# Sheet1.net
KiCad netlist of a schematic drawn in Altium Designer
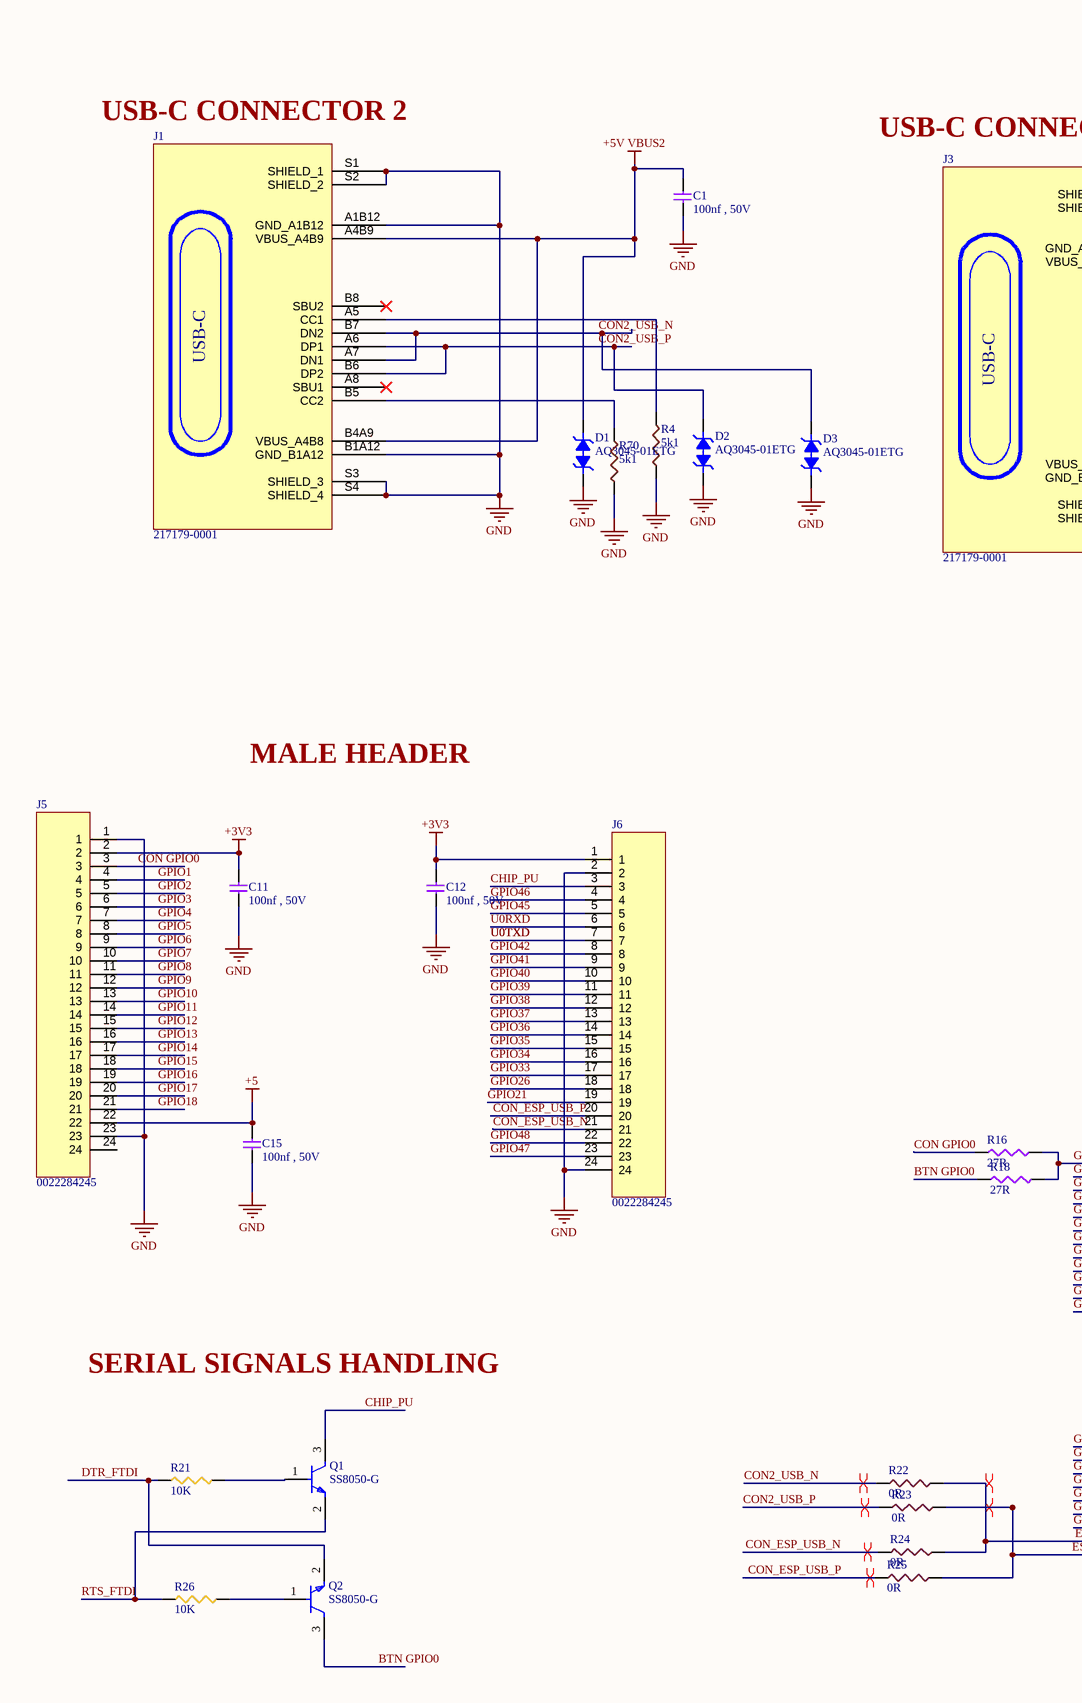
[diagram p0: Sheet1.SchDoc, left]
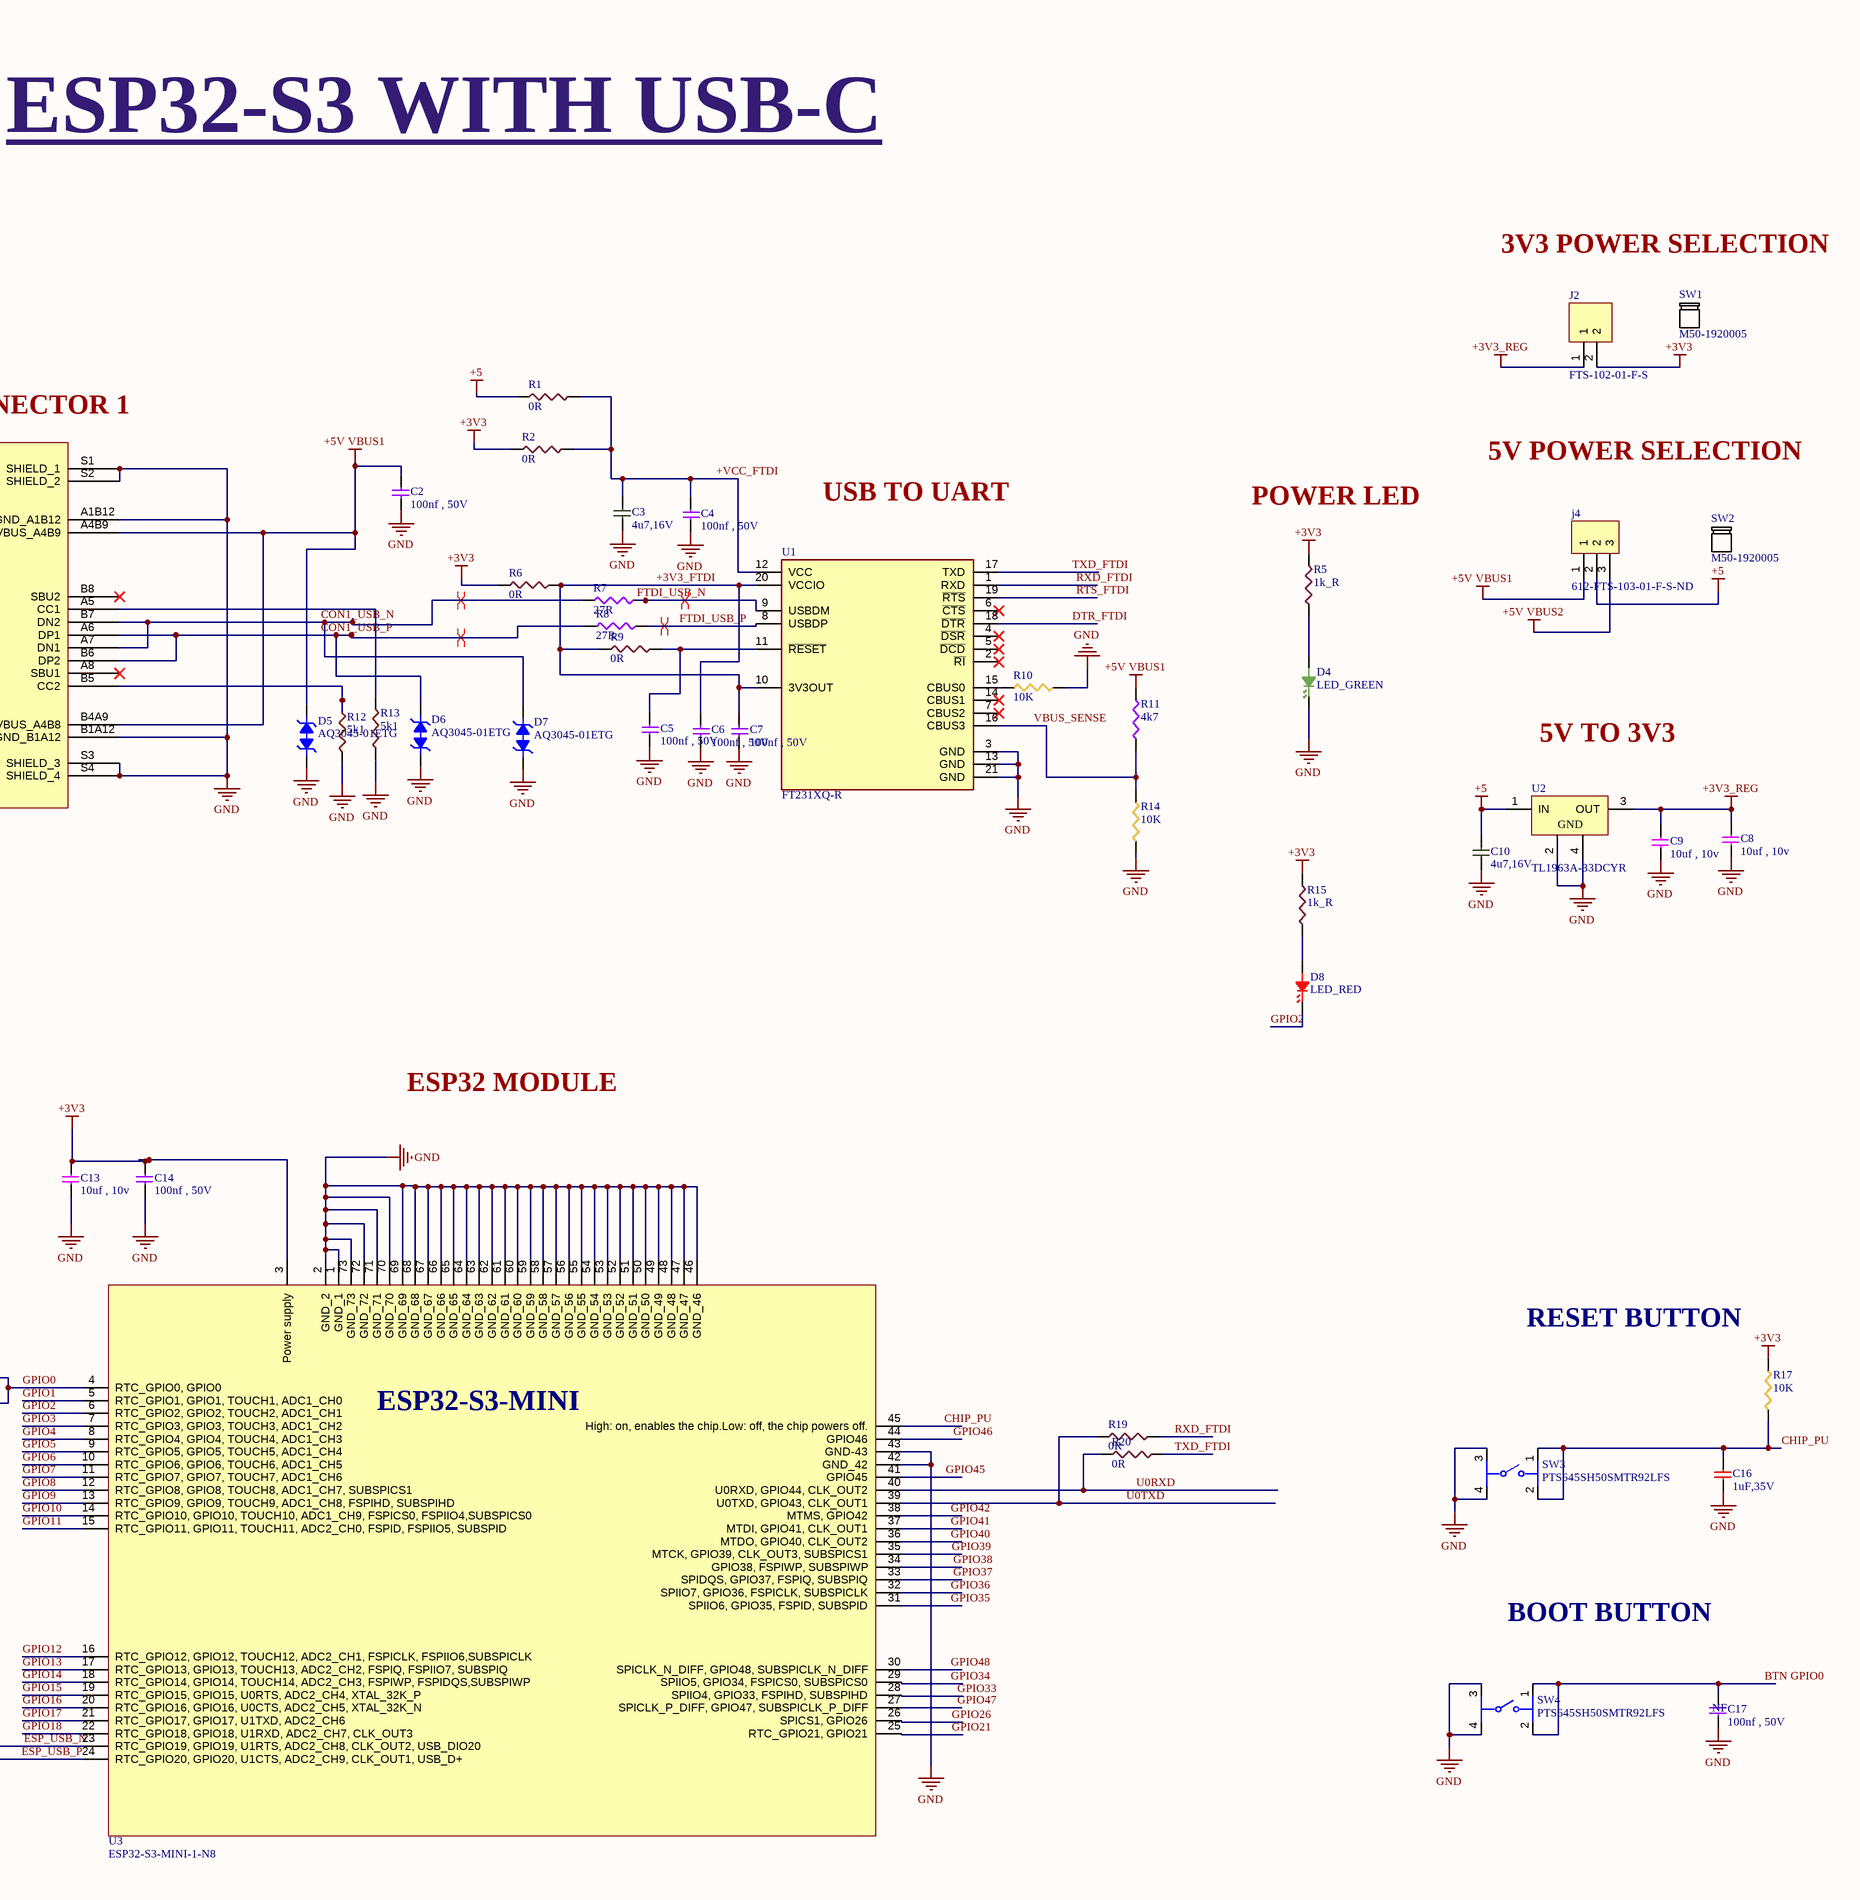
[diagram p1: Sheet1.SchDoc, right]

(export (version "E")
  (design (tool "Eeschema 10.0.6"))
  (components
    (comp (ref "C1")
      (value "100nf , 50V")
      (footprint "CAPC1005X55N")
      (fields
        (field (name "MANUFACTURER") "Samsung")
        (field (name "MANUFACTURER PART NUMBER") "CL05B104KB5NNNC")
        (field (name "TOLERANCE") "10%")
      )
      (libsource (lib "Schlib4") (part "CL05B104KB5NNNC"))
    )
    (comp (ref "C2")
      (value "100nf , 50V")
      (footprint "CAPC1005X55N")
      (fields
        (field (name "MANUFACTURER") "Samsung")
        (field (name "MANUFACTURER PART NUMBER") "CL05B104KB5NNNC")
        (field (name "TOLERANCE") "10%")
      )
      (libsource (lib "Schlib4") (part "CL05B104KB5NNNC"))
    )
    (comp (ref "C3")
      (value "4u7,16V")
      (footprint "CAPC1005X55N")
      (description "Multilayer Ceramic Capacitor, 4.7 uF, 16 V, ± 20%, X5R, 0402 [1005 Metric]")
      (fields
        (field (name "MANUFACTURER") "Samsung")
        (field (name "MANUFACTURER PART NUMBER") "CL05A475MO5NUNC")
      )
      (libsource (lib "Schlib4") (part "CL05A475MO5NUNC"))
    )
    (comp (ref "C4")
      (value "100nf , 50V")
      (footprint "CAPC1005X55N")
      (fields
        (field (name "MANUFACTURER") "Samsung")
        (field (name "MANUFACTURER PART NUMBER") "CL05B104KB5NNNC")
        (field (name "TOLERANCE") "10%")
      )
      (libsource (lib "Schlib4") (part "CL05B104KB5NNNC"))
    )
    (comp (ref "C5")
      (value "100nf , 50V")
      (footprint "CAPC1005X55N")
      (fields
        (field (name "MANUFACTURER") "Samsung")
        (field (name "MANUFACTURER PART NUMBER") "CL05B104KB5NNNC")
        (field (name "TOLERANCE") "10%")
      )
      (libsource (lib "Schlib4") (part "CL05B104KB5NNNC"))
    )
    (comp (ref "C6")
      (value "100nf , 50V")
      (footprint "CAPC1005X55N")
      (fields
        (field (name "MANUFACTURER") "Samsung")
        (field (name "MANUFACTURER PART NUMBER") "CL05B104KB5NNNC")
        (field (name "TOLERANCE") "10%")
      )
      (libsource (lib "Schlib4") (part "CL05B104KB5NNNC"))
    )
    (comp (ref "C7")
      (value "100nf , 50V")
      (footprint "CAPC1005X55N")
      (fields
        (field (name "MANUFACTURER") "Samsung")
        (field (name "MANUFACTURER PART NUMBER") "CL05B104KB5NNNC")
        (field (name "TOLERANCE") "10%")
      )
      (libsource (lib "Schlib4") (part "CL05B104KB5NNNC"))
    )
    (comp (ref "C8")
      (value "10uf , 10v")
      (footprint "CAPC1005X55N")
      (description "Multilayer Ceramic Capacitor, 10 uF, 10 V, ± 20%, X5R, 0402 [1005 Metric]")
      (fields
        (field (name "MANUFACTURER") "Samsung")
        (field (name "MANUFACTURER PART NUMBER") "CL05A106MP8NUB8")
      )
      (libsource (lib "Schlib4") (part "CL05A106MP8NUB8"))
    )
    (comp (ref "C9")
      (value "10uf , 10v")
      (footprint "CAPC1005X55N")
      (description "Multilayer Ceramic Capacitor, 10 uF, 10 V, ± 20%, X5R, 0402 [1005 Metric]")
      (fields
        (field (name "MANUFACTURER") "Samsung")
        (field (name "MANUFACTURER PART NUMBER") "CL05A106MP8NUB8")
      )
      (libsource (lib "Schlib4") (part "CL05A106MP8NUB8"))
    )
    (comp (ref "C10")
      (value "4u7,16V")
      (footprint "CAPC1005X55N")
      (description "Multilayer Ceramic Capacitor, 4.7 uF, 16 V, ± 20%, X5R, 0402 [1005 Metric]")
      (fields
        (field (name "MANUFACTURER") "Samsung")
        (field (name "MANUFACTURER PART NUMBER") "CL05A475MO5NUNC")
      )
      (libsource (lib "Schlib4") (part "CL05A475MO5NUNC"))
    )
    (comp (ref "C11")
      (value "100nf , 50V")
      (footprint "CAPC1005X55N")
      (fields
        (field (name "MANUFACTURER") "Samsung")
        (field (name "MANUFACTURER PART NUMBER") "CL05B104KB5NNNC")
        (field (name "TOLERANCE") "10%")
      )
      (libsource (lib "Schlib4") (part "CL05B104KB5NNNC"))
    )
    (comp (ref "C12")
      (value "100nf , 50V")
      (footprint "CAPC1005X55N")
      (fields
        (field (name "MANUFACTURER") "Samsung")
        (field (name "MANUFACTURER PART NUMBER") "CL05B104KB5NNNC")
        (field (name "TOLERANCE") "10%")
      )
      (libsource (lib "Schlib4") (part "CL05B104KB5NNNC"))
    )
    (comp (ref "C13")
      (value "10uf , 10v")
      (footprint "CAPC1005X55N")
      (description "Multilayer Ceramic Capacitor, 10 uF, 10 V, ± 20%, X5R, 0402 [1005 Metric]")
      (fields
        (field (name "MANUFACTURER") "Samsung")
        (field (name "MANUFACTURER PART NUMBER") "CL05A106MP8NUB8")
      )
      (libsource (lib "Schlib4") (part "CL05A106MP8NUB8"))
    )
    (comp (ref "C14")
      (value "100nf , 50V")
      (footprint "CAPC1005X55N")
      (fields
        (field (name "MANUFACTURER") "Samsung")
        (field (name "MANUFACTURER PART NUMBER") "CL05B104KB5NNNC")
        (field (name "TOLERANCE") "10%")
      )
      (libsource (lib "Schlib4") (part "CL05B104KB5NNNC"))
    )
    (comp (ref "C15")
      (value "100nf , 50V")
      (footprint "CAPC1005X55N")
      (fields
        (field (name "MANUFACTURER") "Samsung")
        (field (name "MANUFACTURER PART NUMBER") "CL05B104KB5NNNC")
        (field (name "TOLERANCE") "10%")
      )
      (libsource (lib "Schlib4") (part "CL05B104KB5NNNC"))
    )
    (comp (ref "C16")
      (value "1uF,35V")
      (footprint "CAPC1005X55N")
      (fields
        (field (name "MANUFACTURER") "Samsung")
        (field (name "MANUFACTURER PART NUMBER") "CL05A105KL5NRNC")
        (field (name "TOLERANCE") "10%")
      )
      (libsource (lib "Schlib4") (part "CL05A105KL5NRNC"))
    )
    (comp (ref "C17")
      (value "100nf , 50V")
      (footprint "CAPC1005X55N")
      (fields
        (field (name "MANUFACTURER") "Samsung")
        (field (name "MANUFACTURER PART NUMBER") "CL05B104KB5NNNC")
        (field (name "TOLERANCE") "10%")
      )
      (libsource (lib "Schlib4") (part "CL05B104KB5NNNC"))
    )
    (comp (ref "D1")
      (value "AQ3045-01ETG")
      (footprint "AQ3045-01ETG")
      (description "TVS DIODE 12VC 3A SOD882 / ESD Suppressor TVS Bi-Dir 5.3V Automotive 2-Pin SOD-882 T/R")
      (fields (field (name "MANUFACTURER") "Littelfuse"))
      (libsource (lib "Schlib4") (part "AQ3045-01ETG"))
    )
    (comp (ref "D2")
      (value "AQ3045-01ETG")
      (footprint "AQ3045-01ETG")
      (description "TVS DIODE 12VC 3A SOD882 / ESD Suppressor TVS Bi-Dir 5.3V Automotive 2-Pin SOD-882 T/R")
      (fields (field (name "MANUFACTURER") "Littelfuse"))
      (libsource (lib "Schlib4") (part "AQ3045-01ETG"))
    )
    (comp (ref "D3")
      (value "AQ3045-01ETG")
      (footprint "AQ3045-01ETG")
      (description "TVS DIODE 12VC 3A SOD882 / ESD Suppressor TVS Bi-Dir 5.3V Automotive 2-Pin SOD-882 T/R")
      (fields (field (name "MANUFACTURER") "Littelfuse"))
      (libsource (lib "Schlib4") (part "AQ3045-01ETG"))
    )
    (comp (ref "D4")
      (value "LED_GREEN")
      (footprint "LED_0402_GRN - duplicate")
      (description "LED Uni-Color Yellow Green 574nm 2-Pin Chip 0402(1006Metric) T/R")
      (fields
        (field (name "MANUFACTURER") "Vishay")
        (field (name "MANUFACTURER PART NUMBER") "VLMG1500-GS08")
      )
      (libsource (lib "Schlib4") (part "VLMG1500-GS08"))
    )
    (comp (ref "D5")
      (value "AQ3045-01ETG")
      (footprint "AQ3045-01ETG")
      (description "TVS DIODE 12VC 3A SOD882 / ESD Suppressor TVS Bi-Dir 5.3V Automotive 2-Pin SOD-882 T/R")
      (fields (field (name "MANUFACTURER") "Littelfuse"))
      (libsource (lib "Schlib4") (part "AQ3045-01ETG"))
    )
    (comp (ref "D6")
      (value "AQ3045-01ETG")
      (footprint "AQ3045-01ETG")
      (description "TVS DIODE 12VC 3A SOD882 / ESD Suppressor TVS Bi-Dir 5.3V Automotive 2-Pin SOD-882 T/R")
      (fields (field (name "MANUFACTURER") "Littelfuse"))
      (libsource (lib "Schlib4") (part "AQ3045-01ETG"))
    )
    (comp (ref "D7")
      (value "AQ3045-01ETG")
      (footprint "AQ3045-01ETG")
      (description "TVS DIODE 12VC 3A SOD882 / ESD Suppressor TVS Bi-Dir 5.3V Automotive 2-Pin SOD-882 T/R")
      (fields (field (name "MANUFACTURER") "Littelfuse"))
      (libsource (lib "Schlib4") (part "AQ3045-01ETG"))
    )
    (comp (ref "D8")
      (value "LED_RED")
      (footprint "LED_0402_RED")
      (description "LED Uni-Color Super Red 639nm 2-Pin Chip 0402(1006Metric) T/R")
      (fields
        (field (name "MANUFACTURER") "Vishay")
        (field (name "MANUFACTURER PART NUMBER") "VLMS1500-GS08")
      )
      (libsource (lib "Schlib4") (part "VLMS1500-GS08"))
    )
    (comp (ref "J1")
      (value "217179-0001")
      (footprint "FP-2171790001-MFG")
      (description "USB Connector, 16 Contact(s), Female, Right Angle, Surface Mount Terminal, Locking, Receptacle")
      (fields (field (name "MANUFACTURER") "Molex"))
      (libsource (lib "Schlib4") (part "217179-0001"))
    )
    (comp (ref "J2")
      (value "FTS-102-01-F-S")
      (footprint "HDR_1X2")
      (description "Conn Unshrouded Header HDR 2 POS 1.27mm Solder ST Top Entry Thru-Hole Layer")
      (fields (field (name "MANUFACTURER") "Samtec"))
      (libsource (lib "Schlib4") (part "FTS-102-01-F-S"))
    )
    (comp (ref "J3")
      (value "217179-0001")
      (footprint "FP-2171790001-MFG")
      (description "USB Connector, 16 Contact(s), Female, Right Angle, Surface Mount Terminal, Locking, Receptacle")
      (fields (field (name "MANUFACTURER") "Molex"))
      (libsource (lib "Schlib4") (part "217179-0001"))
    )
    (comp (ref "j4")
      (value "612-FTS-103-01-F-S-ND")
      (footprint "HDR_1X3 - duplicate")
      (description "Conn Unshrouded Header HDR 3 POS 1.27mm Solder ST Thru-Hole")
      (fields
        (field (name "MANUFACTURER") "Samtec")
        (field (name "MANUFACTURER PART NUMBER") "FTS-103-01-F-S")
      )
      (libsource (lib "Schlib4") (part "FTS-103-01-F-S"))
    )
    (comp (ref "J5")
      (value "0022284245")
      (footprint "HDR_1X24_2.54mm")
      (description "Conn Unshrouded Header HDR 24 POS 2.54mm Solder ST Top Entry Thru-Hole KK® Bag")
      (fields (field (name "MANUFACTURER") "Molex"))
      (libsource (lib "Schlib4") (part "0022284245"))
    )
    (comp (ref "J6")
      (value "0022284245")
      (footprint "HDR_1X24_2.54mm")
      (description "Conn Unshrouded Header HDR 24 POS 2.54mm Solder ST Top Entry Thru-Hole KK® Bag")
      (fields (field (name "MANUFACTURER") "Molex"))
      (libsource (lib "") (part "0022284245_1"))
    )
    (comp (ref "Q1")
      (value "SS8050-G")
      (footprint "PCBComponent_1")
      (description "Trans Gp Bjt NPN 25V 1.5A 300MW 3-PIN SOT-23 T/r")
      (fields (field (name "MANUFACTURER") "Comchip"))
      (libsource (lib "Schlib4") (part "SS8050-G"))
    )
    (comp (ref "Q2")
      (value "SS8050-G")
      (footprint "PCBComponent_1")
      (description "Trans Gp Bjt NPN 25V 1.5A 300MW 3-PIN SOT-23 T/r")
      (fields (field (name "MANUFACTURER") "Comchip"))
      (libsource (lib "Schlib4") (part "SS8050-G"))
    )
    (comp (ref "R1")
      (value "0R")
      (footprint "RESC1005X37N")
      (description "RC Series 0402 0 Ohms 0.03 W Jumper Surface Mount Thick Film Chip Resistor")
      (fields
        (field (name "MANUFACTURER") "Samsung")
        (field (name "MANUFACTURER PART NUMBER") "RC0402J000CS")
      )
      (libsource (lib "Schlib4") (part "RC0402J000CS"))
    )
    (comp (ref "R2")
      (value "0R")
      (footprint "RESC1005X37N")
      (description "RC Series 0402 0 Ohms 0.03 W Jumper Surface Mount Thick Film Chip Resistor")
      (fields
        (field (name "MANUFACTURER") "Samsung")
        (field (name "MANUFACTURER PART NUMBER") "RC0402J000CS")
      )
      (libsource (lib "Schlib4") (part "RC0402J000CS"))
    )
    (comp (ref "R4")
      (value "5k1")
      (footprint "RESC1005X37N")
      (description "SMD Chip Resistor, 5.1 kOhm, ± 1%, 63 mW, 0402 [1005 Metric], Thick Film, General Purpose")
      (fields
        (field (name "MANUFACTURER") "Yageo")
        (field (name "MANUFACTURER PART NUMBER") "AC0402FR-075K1L")
      )
      (libsource (lib "Schlib4") (part "AC0402FR-075K1L"))
    )
    (comp (ref "R5")
      (value "1k_R")
      (footprint "RESC1005X37N")
      (description "Res Thick Film 0402 1K Ohm 1% 1/16W ±100ppm/°C Molded SMD Punched Paper T/R")
      (fields
        (field (name "MANUFACTURER") "Samsung")
        (field (name "MANUFACTURER PART NUMBER") "RCS1005F102CS")
      )
      (libsource (lib "Schlib4") (part "RCS1005F102CS"))
    )
    (comp (ref "R6")
      (value "0R")
      (footprint "RESC1005X37N")
      (description "RC Series 0402 0 Ohms 0.03 W Jumper Surface Mount Thick Film Chip Resistor")
      (fields
        (field (name "MANUFACTURER") "Samsung")
        (field (name "MANUFACTURER PART NUMBER") "RC0402J000CS")
      )
      (libsource (lib "Schlib4") (part "RC0402J000CS"))
    )
    (comp (ref "R7")
      (value "27R")
      (footprint "RESC1005X37N")
      (description "SMD Chip Resistor, 27 Ohm, ï¿½ 1%, 62.5 mW, 0402 [1005 Metric], Thick Film, General Purpose")
      (fields
        (field (name "MANUFACTURER") "Yageo")
        (field (name "MANUFACTURER PART NUMBER") "RC0402FR-0727RL")
      )
      (libsource (lib "Schlib4") (part "RC0402FR-0727RL"))
    )
    (comp (ref "R8")
      (value "27R")
      (footprint "RESC1005X37N")
      (description "SMD Chip Resistor, 27 Ohm, ï¿½ 1%, 62.5 mW, 0402 [1005 Metric], Thick Film, General Purpose")
      (fields
        (field (name "MANUFACTURER") "Yageo")
        (field (name "MANUFACTURER PART NUMBER") "RC0402FR-0727RL")
      )
      (libsource (lib "Schlib4") (part "RC0402FR-0727RL"))
    )
    (comp (ref "R9")
      (value "0R")
      (footprint "RESC1005X37N")
      (description "RC Series 0402 0 Ohms 0.03 W Jumper Surface Mount Thick Film Chip Resistor")
      (fields
        (field (name "MANUFACTURER") "Samsung")
        (field (name "MANUFACTURER PART NUMBER") "RC0402J000CS")
      )
      (libsource (lib "Schlib4") (part "RC0402J000CS"))
    )
    (comp (ref "R10")
      (value "10K")
      (footprint "RESC1005X37N")
      (description "SMD Chip Resistor, 10 kOhm, ï¿½ 1%, 62.5 mW, 0402 [1005 Metric], Thick Film, General Purpose")
      (fields
        (field (name "MANUFACTURER") "Yageo")
        (field (name "MANUFACTURER PART NUMBER") "AC0402FR-0710KL")
      )
      (libsource (lib "Schlib4") (part "AC0402FR-0710KL"))
    )
    (comp (ref "R11")
      (value "4k7")
      (footprint "RESC1005X37N")
      (description "SMD Chip Resistor, 4.7 kOhm, ï¿½ 1%, 62.5 mW, 0402 [1005 Metric], Thick Film, General Purpose")
      (fields
        (field (name "MANUFACTURER") "Yageo")
        (field (name "MANUFACTURER PART NUMBER") "RC0402FR-074K7L")
      )
      (libsource (lib "Schlib4") (part "RC0402FR-074K7L"))
    )
    (comp (ref "R12")
      (value "5k1")
      (footprint "RESC1005X37N")
      (description "SMD Chip Resistor, 5.1 kOhm, ± 1%, 63 mW, 0402 [1005 Metric], Thick Film, General Purpose")
      (fields
        (field (name "MANUFACTURER") "Yageo")
        (field (name "MANUFACTURER PART NUMBER") "AC0402FR-075K1L")
      )
      (libsource (lib "Schlib4") (part "AC0402FR-075K1L"))
    )
    (comp (ref "R13")
      (value "5k1")
      (footprint "RESC1005X37N")
      (description "SMD Chip Resistor, 5.1 kOhm, ± 1%, 63 mW, 0402 [1005 Metric], Thick Film, General Purpose")
      (fields
        (field (name "MANUFACTURER") "Yageo")
        (field (name "MANUFACTURER PART NUMBER") "AC0402FR-075K1L")
      )
      (libsource (lib "Schlib4") (part "AC0402FR-075K1L"))
    )
    (comp (ref "R14")
      (value "10K")
      (footprint "RESC1005X37N")
      (description "SMD Chip Resistor, 10 kOhm, ï¿½ 1%, 62.5 mW, 0402 [1005 Metric], Thick Film, General Purpose")
      (fields
        (field (name "MANUFACTURER") "Yageo")
        (field (name "MANUFACTURER PART NUMBER") "AC0402FR-0710KL")
      )
      (libsource (lib "Schlib4") (part "AC0402FR-0710KL"))
    )
    (comp (ref "R15")
      (value "1k_R")
      (footprint "RESC1005X37N")
      (description "Res Thick Film 0402 1K Ohm 1% 1/16W ±100ppm/°C Molded SMD Punched Paper T/R")
      (fields
        (field (name "MANUFACTURER") "Samsung")
        (field (name "MANUFACTURER PART NUMBER") "RCS1005F102CS")
      )
      (libsource (lib "Schlib4") (part "RCS1005F102CS"))
    )
    (comp (ref "R16")
      (value "27R")
      (footprint "RESC1005X37N")
      (description "SMD Chip Resistor, 27 Ohm, ï¿½ 1%, 62.5 mW, 0402 [1005 Metric], Thick Film, General Purpose")
      (fields
        (field (name "MANUFACTURER") "Yageo")
        (field (name "MANUFACTURER PART NUMBER") "RC0402FR-0727RL")
      )
      (libsource (lib "Schlib4") (part "RC0402FR-0727RL"))
    )
    (comp (ref "R17")
      (value "10K")
      (footprint "RESC1005X37N")
      (description "SMD Chip Resistor, 10 kOhm, ï¿½ 1%, 62.5 mW, 0402 [1005 Metric], Thick Film, General Purpose")
      (fields
        (field (name "MANUFACTURER") "Yageo")
        (field (name "MANUFACTURER PART NUMBER") "AC0402FR-0710KL")
      )
      (libsource (lib "Schlib4") (part "AC0402FR-0710KL"))
    )
    (comp (ref "R18")
      (value "27R")
      (footprint "RESC1005X37N")
      (description "SMD Chip Resistor, 27 Ohm, ï¿½ 1%, 62.5 mW, 0402 [1005 Metric], Thick Film, General Purpose")
      (fields
        (field (name "MANUFACTURER") "Yageo")
        (field (name "MANUFACTURER PART NUMBER") "RC0402FR-0727RL")
      )
      (libsource (lib "Schlib4") (part "RC0402FR-0727RL"))
    )
    (comp (ref "R19")
      (value "0R")
      (footprint "RESC1005X37N")
      (description "RC Series 0402 0 Ohms 0.03 W Jumper Surface Mount Thick Film Chip Resistor")
      (fields
        (field (name "MANUFACTURER") "Samsung")
        (field (name "MANUFACTURER PART NUMBER") "RC0402J000CS")
      )
      (libsource (lib "Schlib4") (part "RC0402J000CS"))
    )
    (comp (ref "R20")
      (value "0R")
      (footprint "RESC1005X37N")
      (description "RC Series 0402 0 Ohms 0.03 W Jumper Surface Mount Thick Film Chip Resistor")
      (fields
        (field (name "MANUFACTURER") "Samsung")
        (field (name "MANUFACTURER PART NUMBER") "RC0402J000CS")
      )
      (libsource (lib "Schlib4") (part "RC0402J000CS"))
    )
    (comp (ref "R21")
      (value "10K")
      (footprint "RESC1005X37N")
      (description "SMD Chip Resistor, 10 kOhm, ï¿½ 1%, 62.5 mW, 0402 [1005 Metric], Thick Film, General Purpose")
      (fields
        (field (name "MANUFACTURER") "Yageo")
        (field (name "MANUFACTURER PART NUMBER") "AC0402FR-0710KL")
      )
      (libsource (lib "Schlib4") (part "AC0402FR-0710KL"))
    )
    (comp (ref "R22")
      (value "0R")
      (footprint "RESC1005X37N")
      (description "RC Series 0402 0 Ohms 0.03 W Jumper Surface Mount Thick Film Chip Resistor")
      (fields
        (field (name "MANUFACTURER") "Samsung")
        (field (name "MANUFACTURER PART NUMBER") "RC0402J000CS")
      )
      (libsource (lib "Schlib4") (part "RC0402J000CS"))
    )
    (comp (ref "R23")
      (value "0R")
      (footprint "RESC1005X37N")
      (description "RC Series 0402 0 Ohms 0.03 W Jumper Surface Mount Thick Film Chip Resistor")
      (fields
        (field (name "MANUFACTURER") "Samsung")
        (field (name "MANUFACTURER PART NUMBER") "RC0402J000CS")
      )
      (libsource (lib "Schlib4") (part "RC0402J000CS"))
    )
    (comp (ref "R24")
      (value "0R")
      (footprint "RESC1005X37N")
      (description "RC Series 0402 0 Ohms 0.03 W Jumper Surface Mount Thick Film Chip Resistor")
      (fields
        (field (name "MANUFACTURER") "Samsung")
        (field (name "MANUFACTURER PART NUMBER") "RC0402J000CS")
      )
      (libsource (lib "Schlib4") (part "RC0402J000CS"))
    )
    (comp (ref "R25")
      (value "0R")
      (footprint "RESC1005X37N")
      (description "RC Series 0402 0 Ohms 0.03 W Jumper Surface Mount Thick Film Chip Resistor")
      (fields
        (field (name "MANUFACTURER") "Samsung")
        (field (name "MANUFACTURER PART NUMBER") "RC0402J000CS")
      )
      (libsource (lib "Schlib4") (part "RC0402J000CS"))
    )
    (comp (ref "R26")
      (value "10K")
      (footprint "RESC1005X37N")
      (description "SMD Chip Resistor, 10 kOhm, ï¿½ 1%, 62.5 mW, 0402 [1005 Metric], Thick Film, General Purpose")
      (fields
        (field (name "MANUFACTURER") "Yageo")
        (field (name "MANUFACTURER PART NUMBER") "AC0402FR-0710KL")
      )
      (libsource (lib "Schlib4") (part "AC0402FR-0710KL"))
    )
    (comp (ref "R70")
      (value "5k1")
      (footprint "RESC1005X37N")
      (description "SMD Chip Resistor, 5.1 kOhm, ± 1%, 63 mW, 0402 [1005 Metric], Thick Film, General Purpose")
      (fields
        (field (name "MANUFACTURER") "Yageo")
        (field (name "MANUFACTURER PART NUMBER") "AC0402FR-075K1L")
      )
      (libsource (lib "Schlib4") (part "AC0402FR-075K1L"))
    )
    (comp (ref "SW1")
      (value "M50-1920005")
      (description "Jumper (Busbar), Jumper Socket, Pin Headers, 2, 1.27 Mm Rohs Compliant: Yes ¦Harwin M50-1920005")
      (fields (field (name "MANUFACTURER") "Harwin"))
      (libsource (lib "Schlib4") (part "M50-1920005"))
    )
    (comp (ref "SW2")
      (value "M50-1920005")
      (description "Jumper (Busbar), Jumper Socket, Pin Headers, 2, 1.27 Mm Rohs Compliant: Yes ¦Harwin M50-1920005")
      (fields (field (name "MANUFACTURER") "Harwin"))
      (libsource (lib "Schlib4") (part "M50-1920005"))
    )
    (comp (ref "SW3")
      (value "PTS645SH50SMTR92LFS")
      (footprint "FP-PTS645SH50SMTR92LFS-MFG")
      (description "Switch Tactile N.O. SPST Round Button Gull Wing 0.05A 12VDC 100000Cycles 1.96N SMD T/R")
      (fields (field (name "MANUFACTURER") "ITT C&K"))
      (libsource (lib "Schlib4") (part "PTS645SH50SMTR92LFS"))
    )
    (comp (ref "SW4")
      (value "PTS645SH50SMTR92LFS")
      (footprint "FP-PTS645SH50SMTR92LFS-MFG")
      (description "Switch Tactile N.O. SPST Round Button Gull Wing 0.05A 12VDC 100000Cycles 1.96N SMD T/R")
      (fields (field (name "MANUFACTURER") "ITT C&K"))
      (libsource (lib "Schlib4") (part "PTS645SH50SMTR92LFS"))
    )
    (comp (ref "U1")
      (value "FT231XQ-R")
      (footprint "FP-QFN-20-IPC_B")
      (description "USB to Full Handshake UART Interface QFN20 Reel (not offered in your region)")
      (fields (field (name "MANUFACTURER") "FTDI"))
      (libsource (lib "Schlib4") (part "FT231XQ-R"))
    )
    (comp (ref "U2")
      (value "TL1963A-33DCYR")
      (footprint "DCY0004A_N")
      (description "LDO Regulator Pos 3.3V 1.5A 4-Pin(3+Tab) SOT-223 T/R")
      (fields (field (name "MANUFACTURER") "Texas Instruments"))
      (libsource (lib "Schlib4") (part "TL1963A-33DCYR"))
    )
    (comp (ref "U3")
      (value "ESP32-S3-MINI-1-N8")
      (footprint "XCVR_ESP32-S3-MINI-1-N8")
      (description "SMD module, ESP32-S3FN8, 8 MB SPI flash, PCB antenna")
      (fields (field (name "MANUFACTURER") "Espressif Systems"))
      (libsource (lib "Schlib4") (part "ESP32-S3-MINI-1-N8"))
    )
  )
  (nets
    (net (code "1") (name "+3V3") (class "Default")
      (node (ref "C11") (pin "2") (pinfunction "2_2") (pintype "passive"))
      (node (ref "C12") (pin "2") (pinfunction "2_2") (pintype "passive"))
      (node (ref "C13") (pin "2") (pinfunction "2_2") (pintype "passive"))
      (node (ref "C14") (pin "2") (pinfunction "2_2") (pintype "passive"))
      (node (ref "J2") (pin "2") (pinfunction "2_2") (pintype "passive"))
      (node (ref "J5") (pin "2") (pinfunction "2_2") (pintype "passive"))
      (node (ref "J6") (pin "1") (pinfunction "1_1") (pintype "passive"))
      (node (ref "R15") (pin "2") (pinfunction "2_2") (pintype "passive"))
      (node (ref "R17") (pin "2") (pinfunction "2_2") (pintype "passive"))
      (node (ref "R2") (pin "1") (pinfunction "1_1") (pintype "passive"))
      (node (ref "R5") (pin "2") (pinfunction "2_2") (pintype "passive"))
      (node (ref "R6") (pin "1") (pinfunction "1_1") (pintype "passive"))
      (node (ref "U3") (pin "3") (pinfunction "Power_supply_3") (pintype "passive"))
    )
    (net (code "2") (name "+3V3_REG") (class "Default")
      (node (ref "C8") (pin "2") (pinfunction "2_2") (pintype "passive"))
      (node (ref "C9") (pin "2") (pinfunction "2_2") (pintype "passive"))
      (node (ref "J2") (pin "1") (pinfunction "1_1") (pintype "passive"))
      (node (ref "U2") (pin "3") (pinfunction "OUT_3") (pintype "power_in"))
    )
    (net (code "3") (name "+5") (class "Default")
      (node (ref "C10") (pin "2") (pinfunction "2_2") (pintype "passive"))
      (node (ref "C15") (pin "2") (pinfunction "2_2") (pintype "passive"))
      (node (ref "J5") (pin "22") (pinfunction "22_22") (pintype "passive"))
      (node (ref "R1") (pin "1") (pinfunction "1_1") (pintype "passive"))
      (node (ref "U2") (pin "1") (pinfunction "IN_1") (pintype "power_in"))
      (node (ref "j4") (pin "2") (pinfunction "2_2") (pintype "passive"))
    )
    (net (code "4") (name "+5V VBUS1") (class "Default")
      (node (ref "C2") (pin "2") (pinfunction "2_2") (pintype "passive"))
      (node (ref "D5") (pin "2") (pinfunction "2_2") (pintype "passive"))
      (node (ref "J3") (pin "A4B9") (pinfunction "VBUS_A4B9_A4B9") (pintype "passive"))
      (node (ref "J3") (pin "B4A9") (pinfunction "VBUS_A4B8_B4A9") (pintype "passive"))
      (node (ref "R11") (pin "2") (pinfunction "2_2") (pintype "passive"))
      (node (ref "j4") (pin "1") (pinfunction "1_1") (pintype "passive"))
    )
    (net (code "5") (name "+5V VBUS2") (class "Default")
      (node (ref "C1") (pin "2") (pinfunction "2_2") (pintype "passive"))
      (node (ref "D1") (pin "2") (pinfunction "2_2") (pintype "passive"))
      (node (ref "J1") (pin "A4B9") (pinfunction "VBUS_A4B9_A4B9") (pintype "passive"))
      (node (ref "J1") (pin "B4A9") (pinfunction "VBUS_A4B8_B4A9") (pintype "passive"))
      (node (ref "j4") (pin "3") (pinfunction "3_3") (pintype "passive"))
    )
    (net (code "6") (name "/+3V3_FTDI") (class "Default")
      (node (ref "C6") (pin "1") (pinfunction "1_1") (pintype "passive"))
      (node (ref "C7") (pin "1") (pinfunction "1_1") (pintype "passive"))
      (node (ref "R6") (pin "2") (pinfunction "2_2") (pintype "passive"))
      (node (ref "R9") (pin "1") (pinfunction "1_1") (pintype "passive"))
      (node (ref "U1") (pin "10") (pinfunction "3V3OUT_10") (pintype "passive"))
      (node (ref "U1") (pin "20") (pinfunction "VCCIO_20") (pintype "passive"))
    )
    (net (code "7") (name "/+VCC_FTDI") (class "Default")
      (node (ref "C3") (pin "2") (pinfunction "2_2") (pintype "passive"))
      (node (ref "C4") (pin "1") (pinfunction "1_1") (pintype "passive"))
      (node (ref "R1") (pin "2") (pinfunction "2_2") (pintype "passive"))
      (node (ref "R2") (pin "2") (pinfunction "2_2") (pintype "passive"))
      (node (ref "U1") (pin "12") (pinfunction "VCC_12") (pintype "passive"))
    )
    (net (code "8") (name "/BTN GPIO0") (class "Default")
      (node (ref "C17") (pin "2") (pinfunction "2_2") (pintype "passive"))
      (node (ref "Q2") (pin "3") (pinfunction "C_3") (pintype "passive"))
      (node (ref "R18") (pin "1") (pinfunction "1_1") (pintype "passive"))
      (node (ref "SW4") (pin "1") (pinfunction "1_1") (pintype "passive"))
      (node (ref "SW4") (pin "2") (pinfunction "2_2") (pintype "passive"))
    )
    (net (code "9") (name "/CHIP_PU") (class "Default")
      (node (ref "C16") (pin "2") (pinfunction "2_2") (pintype "passive"))
      (node (ref "J6") (pin "3") (pinfunction "3_3") (pintype "passive"))
      (node (ref "Q1") (pin "3") (pinfunction "C_3") (pintype "passive"))
      (node (ref "R17") (pin "1") (pinfunction "1_1") (pintype "passive"))
      (node (ref "SW3") (pin "1") (pinfunction "1_1") (pintype "passive"))
      (node (ref "SW3") (pin "2") (pinfunction "2_2") (pintype "passive"))
      (node (ref "U3") (pin "45") (pinfunction "High:_on,_enables_the_chip.Low:_off,_the_chip_powers_off._45") (pintype "passive"))
    )
    (net (code "10") (name "/CON GPIO0") (class "Default")
      (node (ref "J5") (pin "3") (pinfunction "3_3") (pintype "passive"))
      (node (ref "R16") (pin "1") (pinfunction "1_1") (pintype "passive"))
    )
    (net (code "11") (name "/CON1_USB_N") (class "Default")
      (node (ref "D7") (pin "2") (pinfunction "2_2") (pintype "passive"))
      (node (ref "J3") (pin "A7") (pinfunction "DN1_A7") (pintype "passive"))
      (node (ref "J3") (pin "B7") (pinfunction "DN2_B7") (pintype "passive"))
      (node (ref "R7") (pin "1") (pinfunction "1_1") (pintype "passive"))
    )
    (net (code "12") (name "/CON1_USB_P") (class "Default")
      (node (ref "D6") (pin "2") (pinfunction "2_2") (pintype "passive"))
      (node (ref "J3") (pin "A6") (pinfunction "DP1_A6") (pintype "passive"))
      (node (ref "J3") (pin "B6") (pinfunction "DP2_B6") (pintype "passive"))
      (node (ref "R8") (pin "1") (pinfunction "1_1") (pintype "passive"))
    )
    (net (code "13") (name "/CON2_USB_N") (class "Default")
      (node (ref "D3") (pin "2") (pinfunction "2_2") (pintype "passive"))
      (node (ref "J1") (pin "A7") (pinfunction "DN1_A7") (pintype "passive"))
      (node (ref "J1") (pin "B7") (pinfunction "DN2_B7") (pintype "passive"))
      (node (ref "R22") (pin "1") (pinfunction "1_1") (pintype "passive"))
    )
    (net (code "14") (name "/CON2_USB_P") (class "Default")
      (node (ref "D2") (pin "2") (pinfunction "2_2") (pintype "passive"))
      (node (ref "J1") (pin "A6") (pinfunction "DP1_A6") (pintype "passive"))
      (node (ref "J1") (pin "B6") (pinfunction "DP2_B6") (pintype "passive"))
      (node (ref "R23") (pin "1") (pinfunction "1_1") (pintype "passive"))
    )
    (net (code "15") (name "/CON_ESP_USB_N") (class "Default")
      (node (ref "J6") (pin "21") (pinfunction "21_21") (pintype "passive"))
      (node (ref "R24") (pin "1") (pinfunction "1_1") (pintype "passive"))
    )
    (net (code "16") (name "/CON_ESP_USB_P") (class "Default")
      (node (ref "J6") (pin "20") (pinfunction "20_20") (pintype "passive"))
      (node (ref "R25") (pin "1") (pinfunction "1_1") (pintype "passive"))
    )
    (net (code "17") (name "/DTR_FTDI") (class "Default")
      (node (ref "Q2") (pin "2") (pinfunction "E_2") (pintype "passive"))
      (node (ref "R21") (pin "2") (pinfunction "2_2") (pintype "passive"))
      (node (ref "U1") (pin "18") (pinfunction "~{DTR}_18") (pintype "passive"))
    )
    (net (code "18") (name "/ESP_USB_N") (class "Default")
      (node (ref "R22") (pin "2") (pinfunction "2_2") (pintype "passive"))
      (node (ref "R24") (pin "2") (pinfunction "2_2") (pintype "passive"))
      (node (ref "U3") (pin "23") (pinfunction "RTC_GPIO19,_GPIO19,_U1RTS,_ADC2_CH8,_CLK_OUT2,_USB_DIO20_23") (pintype "passive"))
    )
    (net (code "19") (name "/ESP_USB_P") (class "Default")
      (node (ref "R23") (pin "2") (pinfunction "2_2") (pintype "passive"))
      (node (ref "R25") (pin "2") (pinfunction "2_2") (pintype "passive"))
      (node (ref "U3") (pin "24") (pinfunction "RTC_GPIO20,_GPIO20,_U1CTS,_ADC2_CH9,_CLK_OUT1,_USB_D+_24") (pintype "passive"))
    )
    (net (code "20") (name "/FTDI_USB_N") (class "Default")
      (node (ref "R7") (pin "2") (pinfunction "2_2") (pintype "passive"))
      (node (ref "U1") (pin "9") (pinfunction "USBDM_9") (pintype "passive"))
    )
    (net (code "21") (name "/FTDI_USB_P") (class "Default")
      (node (ref "R8") (pin "2") (pinfunction "2_2") (pintype "passive"))
      (node (ref "U1") (pin "8") (pinfunction "USBDP_8") (pintype "passive"))
    )
    (net (code "22") (name "/GPIO0") (class "Default")
      (node (ref "R16") (pin "2") (pinfunction "2_2") (pintype "passive"))
      (node (ref "R18") (pin "2") (pinfunction "2_2") (pintype "passive"))
      (node (ref "U3") (pin "4") (pinfunction "RTC_GPIO0,_GPIO0_4") (pintype "passive"))
    )
    (net (code "23") (name "/GPIO1") (class "Default")
      (node (ref "J5") (pin "4") (pinfunction "4_4") (pintype "passive"))
      (node (ref "U3") (pin "5") (pinfunction "RTC_GPIO1,_GPIO1,_TOUCH1,_ADC1_CH0_5") (pintype "passive"))
    )
    (net (code "24") (name "/GPIO2") (class "Default")
      (node (ref "D8") (pin "1") (pinfunction "1_1") (pintype "passive"))
      (node (ref "J5") (pin "5") (pinfunction "5_5") (pintype "passive"))
      (node (ref "U3") (pin "6") (pinfunction "RTC_GPIO2,_GPIO2,_TOUCH2,_ADC1_CH1_6") (pintype "passive"))
    )
    (net (code "25") (name "/GPIO3") (class "Default")
      (node (ref "J5") (pin "6") (pinfunction "6_6") (pintype "passive"))
      (node (ref "U3") (pin "7") (pinfunction "RTC_GPIO3,_GPIO3,_TOUCH3,_ADC1_CH2_7") (pintype "passive"))
    )
    (net (code "26") (name "/GPIO4") (class "Default")
      (node (ref "J5") (pin "7") (pinfunction "7_7") (pintype "passive"))
      (node (ref "U3") (pin "8") (pinfunction "RTC_GPIO4,_GPIO4,_TOUCH4,_ADC1_CH3_8") (pintype "passive"))
    )
    (net (code "27") (name "/GPIO5") (class "Default")
      (node (ref "J5") (pin "8") (pinfunction "8_8") (pintype "passive"))
      (node (ref "U3") (pin "9") (pinfunction "RTC_GPIO5,_GPIO5,_TOUCH5,_ADC1_CH4_9") (pintype "passive"))
    )
    (net (code "28") (name "/GPIO6") (class "Default")
      (node (ref "J5") (pin "9") (pinfunction "9_9") (pintype "passive"))
      (node (ref "U3") (pin "10") (pinfunction "RTC_GPIO6,_GPIO6,_TOUCH6,_ADC1_CH5_10") (pintype "passive"))
    )
    (net (code "29") (name "/GPIO7") (class "Default")
      (node (ref "J5") (pin "10") (pinfunction "10_10") (pintype "passive"))
      (node (ref "U3") (pin "11") (pinfunction "RTC_GPIO7,_GPIO7,_TOUCH7,_ADC1_CH6_11") (pintype "passive"))
    )
    (net (code "30") (name "/GPIO8") (class "Default")
      (node (ref "J5") (pin "11") (pinfunction "11_11") (pintype "passive"))
      (node (ref "U3") (pin "12") (pinfunction "RTC_GPIO8,_GPIO8,_TOUCH8,_ADC1_CH7,_SUBSPICS1_12") (pintype "passive"))
    )
    (net (code "31") (name "/GPIO9") (class "Default")
      (node (ref "J5") (pin "12") (pinfunction "12_12") (pintype "passive"))
      (node (ref "U3") (pin "13") (pinfunction "RTC_GPIO9,_GPIO9,_TOUCH9,_ADC1_CH8,_FSPIHD,_SUBSPIHD_13") (pintype "passive"))
    )
    (net (code "32") (name "/GPIO10") (class "Default")
      (node (ref "J5") (pin "13") (pinfunction "13_13") (pintype "passive"))
      (node (ref "U3") (pin "14") (pinfunction "RTC_GPIO10,_GPIO10,_TOUCH10,_ADC1_CH9,_FSPICS0,_FSPIIO4,SUBSPICS0_14") (pintype "passive"))
    )
    (net (code "33") (name "/GPIO11") (class "Default")
      (node (ref "J5") (pin "14") (pinfunction "14_14") (pintype "passive"))
      (node (ref "U3") (pin "15") (pinfunction "RTC_GPIO11,_GPIO11,_TOUCH11,_ADC2_CH0,_FSPID,_FSPIIO5,_SUBSPID_15") (pintype "passive"))
    )
    (net (code "34") (name "/GPIO12") (class "Default")
      (node (ref "J5") (pin "15") (pinfunction "15_15") (pintype "passive"))
      (node (ref "U3") (pin "16") (pinfunction "RTC_GPIO12,_GPIO12,_TOUCH12,_ADC2_CH1,_FSPICLK,_FSPIIO6,SUBSPICLK_16") (pintype "passive"))
    )
    (net (code "35") (name "/GPIO13") (class "Default")
      (node (ref "J5") (pin "16") (pinfunction "16_16") (pintype "passive"))
      (node (ref "U3") (pin "17") (pinfunction "RTC_GPIO13,_GPIO13,_TOUCH13,_ADC2_CH2,_FSPIQ,_FSPIIO7,_SUBSPIQ_17") (pintype "passive"))
    )
    (net (code "36") (name "/GPIO14") (class "Default")
      (node (ref "J5") (pin "17") (pinfunction "17_17") (pintype "passive"))
      (node (ref "U3") (pin "18") (pinfunction "RTC_GPIO14,_GPIO14,_TOUCH14,_ADC2_CH3,_FSPIWP,_FSPIDQS,SUBSPIWP_18") (pintype "passive"))
    )
    (net (code "37") (name "/GPIO15") (class "Default")
      (node (ref "J5") (pin "18") (pinfunction "18_18") (pintype "passive"))
      (node (ref "U3") (pin "19") (pinfunction "RTC_GPIO15,_GPIO15,_U0RTS,_ADC2_CH4,_XTAL_32K_P_19") (pintype "passive"))
    )
    (net (code "38") (name "/GPIO16") (class "Default")
      (node (ref "J5") (pin "19") (pinfunction "19_19") (pintype "passive"))
      (node (ref "U3") (pin "20") (pinfunction "RTC_GPIO16,_GPIO16,_U0CTS,_ADC2_CH5,_XTAL_32K_N_20") (pintype "passive"))
    )
    (net (code "39") (name "/GPIO17") (class "Default")
      (node (ref "J5") (pin "20") (pinfunction "20_20") (pintype "passive"))
      (node (ref "U3") (pin "21") (pinfunction "RTC_GPIO17,_GPIO17,_U1TXD,_ADC2_CH6_21") (pintype "passive"))
    )
    (net (code "40") (name "/GPIO18") (class "Default")
      (node (ref "J5") (pin "21") (pinfunction "21_21") (pintype "passive"))
      (node (ref "U3") (pin "22") (pinfunction "RTC_GPIO18,_GPIO18,_U1RXD,_ADC2_CH7,_CLK_OUT3_22") (pintype "passive"))
    )
    (net (code "41") (name "/GPIO21") (class "Default")
      (node (ref "J6") (pin "19") (pinfunction "19_19") (pintype "passive"))
      (node (ref "U3") (pin "25") (pinfunction "RTC_GPIO21,_GPIO21_25") (pintype "passive"))
    )
    (net (code "42") (name "/GPIO26") (class "Default")
      (node (ref "J6") (pin "18") (pinfunction "18_18") (pintype "passive"))
      (node (ref "U3") (pin "26") (pinfunction "SPICS1,_GPIO26_26") (pintype "passive"))
    )
    (net (code "43") (name "/GPIO33") (class "Default")
      (node (ref "J6") (pin "17") (pinfunction "17_17") (pintype "passive"))
      (node (ref "U3") (pin "28") (pinfunction "SPIIO4,_GPIO33,_FSPIHD,_SUBSPIHD_28") (pintype "passive"))
    )
    (net (code "44") (name "/GPIO34") (class "Default")
      (node (ref "J6") (pin "16") (pinfunction "16_16") (pintype "passive"))
      (node (ref "U3") (pin "29") (pinfunction "SPIIO5,_GPIO34,_FSPICS0,_SUBSPICS0_29") (pintype "passive"))
    )
    (net (code "45") (name "/GPIO35") (class "Default")
      (node (ref "J6") (pin "15") (pinfunction "15_15") (pintype "passive"))
      (node (ref "U3") (pin "31") (pinfunction "SPIIO6,_GPIO35,_FSPID,_SUBSPID_31") (pintype "passive"))
    )
    (net (code "46") (name "/GPIO36") (class "Default")
      (node (ref "J6") (pin "14") (pinfunction "14_14") (pintype "passive"))
      (node (ref "U3") (pin "32") (pinfunction "SPIIO7,_GPIO36,_FSPICLK,_SUBSPICLK_32") (pintype "passive"))
    )
    (net (code "47") (name "/GPIO37") (class "Default")
      (node (ref "J6") (pin "13") (pinfunction "13_13") (pintype "passive"))
      (node (ref "U3") (pin "33") (pinfunction "SPIDQS,_GPIO37,_FSPIQ,_SUBSPIQ_33") (pintype "passive"))
    )
    (net (code "48") (name "/GPIO38") (class "Default")
      (node (ref "J6") (pin "12") (pinfunction "12_12") (pintype "passive"))
      (node (ref "U3") (pin "34") (pinfunction "GPIO38,_FSPIWP,_SUBSPIWP_34") (pintype "passive"))
    )
    (net (code "49") (name "/GPIO39") (class "Default")
      (node (ref "J6") (pin "11") (pinfunction "11_11") (pintype "passive"))
      (node (ref "U3") (pin "35") (pinfunction "MTCK,_GPIO39,_CLK_OUT3,_SUBSPICS1_35") (pintype "passive"))
    )
    (net (code "50") (name "/GPIO40") (class "Default")
      (node (ref "J6") (pin "10") (pinfunction "10_10") (pintype "passive"))
      (node (ref "U3") (pin "36") (pinfunction "MTDO,_GPIO40,_CLK_OUT2_36") (pintype "passive"))
    )
    (net (code "51") (name "/GPIO41") (class "Default")
      (node (ref "J6") (pin "9") (pinfunction "9_9") (pintype "passive"))
      (node (ref "U3") (pin "37") (pinfunction "MTDI,_GPIO41,_CLK_OUT1_37") (pintype "passive"))
    )
    (net (code "52") (name "/GPIO42") (class "Default")
      (node (ref "J6") (pin "8") (pinfunction "8_8") (pintype "passive"))
      (node (ref "U3") (pin "38") (pinfunction "MTMS,_GPIO42_38") (pintype "passive"))
    )
    (net (code "53") (name "/GPIO45") (class "Default")
      (node (ref "J6") (pin "5") (pinfunction "5_5") (pintype "passive"))
      (node (ref "U3") (pin "41") (pinfunction "GPIO45_41") (pintype "passive"))
    )
    (net (code "54") (name "/GPIO46") (class "Default")
      (node (ref "J6") (pin "4") (pinfunction "4_4") (pintype "passive"))
      (node (ref "U3") (pin "44") (pinfunction "GPIO46_44") (pintype "passive"))
    )
    (net (code "55") (name "/GPIO47") (class "Default")
      (node (ref "J6") (pin "23") (pinfunction "23_23") (pintype "passive"))
      (node (ref "U3") (pin "27") (pinfunction "SPICLK_P_DIFF,_GPIO47,_SUBSPICLK_P_DIFF_27") (pintype "passive"))
    )
    (net (code "56") (name "/GPIO48") (class "Default")
      (node (ref "J6") (pin "22") (pinfunction "22_22") (pintype "passive"))
      (node (ref "U3") (pin "30") (pinfunction "SPICLK_N_DIFF,_GPIO48,_SUBSPICLK_N_DIFF_30") (pintype "passive"))
    )
    (net (code "57") (name "/RTS_FTDI") (class "Default")
      (node (ref "Q1") (pin "2") (pinfunction "E_2") (pintype "passive"))
      (node (ref "R26") (pin "2") (pinfunction "2_2") (pintype "passive"))
      (node (ref "U1") (pin "19") (pinfunction "~{RTS}_19") (pintype "passive"))
    )
    (net (code "58") (name "/RXD_FTDI") (class "Default")
      (node (ref "R19") (pin "1") (pinfunction "1_1") (pintype "passive"))
      (node (ref "U1") (pin "1") (pinfunction "RXD_1") (pintype "passive"))
    )
    (net (code "59") (name "/TXD_FTDI") (class "Default")
      (node (ref "R20") (pin "2") (pinfunction "2_2") (pintype "passive"))
      (node (ref "U1") (pin "17") (pinfunction "TXD_17") (pintype "passive"))
    )
    (net (code "60") (name "/U0RXD") (class "Default")
      (node (ref "J6") (pin "6") (pinfunction "6_6") (pintype "passive"))
      (node (ref "R20") (pin "1") (pinfunction "1_1") (pintype "passive"))
      (node (ref "U3") (pin "40") (pinfunction "U0RXD,_GPIO44,_CLK_OUT2_40") (pintype "passive"))
    )
    (net (code "61") (name "/U0TXD") (class "Default")
      (node (ref "J6") (pin "7") (pinfunction "7_7") (pintype "passive"))
      (node (ref "R19") (pin "2") (pinfunction "2_2") (pintype "passive"))
      (node (ref "U3") (pin "39") (pinfunction "U0TXD,_GPIO43,_CLK_OUT1_39") (pintype "passive"))
    )
    (net (code "62") (name "/VBUS_SENSE") (class "Default")
      (node (ref "R11") (pin "1") (pinfunction "1_1") (pintype "passive"))
      (node (ref "R14") (pin "2") (pinfunction "2_2") (pintype "passive"))
      (node (ref "U1") (pin "16") (pinfunction "CBUS3_16") (pintype "passive"))
    )
    (net (code "63") (name "GND") (class "Default")
      (node (ref "C1") (pin "1") (pinfunction "1_1") (pintype "passive"))
      (node (ref "C10") (pin "1") (pinfunction "1_1") (pintype "passive"))
      (node (ref "C11") (pin "1") (pinfunction "1_1") (pintype "passive"))
      (node (ref "C12") (pin "1") (pinfunction "1_1") (pintype "passive"))
      (node (ref "C13") (pin "1") (pinfunction "1_1") (pintype "passive"))
      (node (ref "C14") (pin "1") (pinfunction "1_1") (pintype "passive"))
      (node (ref "C15") (pin "1") (pinfunction "1_1") (pintype "passive"))
      (node (ref "C16") (pin "1") (pinfunction "1_1") (pintype "passive"))
      (node (ref "C17") (pin "1") (pinfunction "1_1") (pintype "passive"))
      (node (ref "C2") (pin "1") (pinfunction "1_1") (pintype "passive"))
      (node (ref "C3") (pin "1") (pinfunction "1_1") (pintype "passive"))
      (node (ref "C4") (pin "2") (pinfunction "2_2") (pintype "passive"))
      (node (ref "C5") (pin "2") (pinfunction "2_2") (pintype "passive"))
      (node (ref "C6") (pin "2") (pinfunction "2_2") (pintype "passive"))
      (node (ref "C7") (pin "2") (pinfunction "2_2") (pintype "passive"))
      (node (ref "C8") (pin "1") (pinfunction "1_1") (pintype "passive"))
      (node (ref "C9") (pin "1") (pinfunction "1_1") (pintype "passive"))
      (node (ref "D1") (pin "1") (pinfunction "1_1") (pintype "passive"))
      (node (ref "D2") (pin "1") (pinfunction "1_1") (pintype "passive"))
      (node (ref "D3") (pin "1") (pinfunction "1_1") (pintype "passive"))
      (node (ref "D4") (pin "1") (pinfunction "1_1") (pintype "passive"))
      (node (ref "D5") (pin "1") (pinfunction "1_1") (pintype "passive"))
      (node (ref "D6") (pin "1") (pinfunction "1_1") (pintype "passive"))
      (node (ref "D7") (pin "1") (pinfunction "1_1") (pintype "passive"))
      (node (ref "J1") (pin "A1B12") (pinfunction "GND_A1B12_A1B12") (pintype "passive"))
      (node (ref "J1") (pin "B1A12") (pinfunction "GND_B1A12_B1A12") (pintype "passive"))
      (node (ref "J1") (pin "S1") (pinfunction "SHIELD_1_S1") (pintype "passive"))
      (node (ref "J1") (pin "S2") (pinfunction "SHIELD_2_S2") (pintype "passive"))
      (node (ref "J1") (pin "S3") (pinfunction "SHIELD_3_S3") (pintype "passive"))
      (node (ref "J1") (pin "S4") (pinfunction "SHIELD_4_S4") (pintype "passive"))
      (node (ref "J3") (pin "A1B12") (pinfunction "GND_A1B12_A1B12") (pintype "passive"))
      (node (ref "J3") (pin "B1A12") (pinfunction "GND_B1A12_B1A12") (pintype "passive"))
      (node (ref "J3") (pin "S1") (pinfunction "SHIELD_1_S1") (pintype "passive"))
      (node (ref "J3") (pin "S2") (pinfunction "SHIELD_2_S2") (pintype "passive"))
      (node (ref "J3") (pin "S3") (pinfunction "SHIELD_3_S3") (pintype "passive"))
      (node (ref "J3") (pin "S4") (pinfunction "SHIELD_4_S4") (pintype "passive"))
      (node (ref "J5") (pin "1") (pinfunction "1_1") (pintype "passive"))
      (node (ref "J5") (pin "23") (pinfunction "23_23") (pintype "passive"))
      (node (ref "J6") (pin "2") (pinfunction "2_2") (pintype "passive"))
      (node (ref "J6") (pin "24") (pinfunction "24_24") (pintype "passive"))
      (node (ref "R10") (pin "1") (pinfunction "1_1") (pintype "passive"))
      (node (ref "R12") (pin "1") (pinfunction "1_1") (pintype "passive"))
      (node (ref "R13") (pin "1") (pinfunction "1_1") (pintype "passive"))
      (node (ref "R14") (pin "1") (pinfunction "1_1") (pintype "passive"))
      (node (ref "R4") (pin "1") (pinfunction "1_1") (pintype "passive"))
      (node (ref "R70") (pin "1") (pinfunction "1_1") (pintype "passive"))
      (node (ref "SW3") (pin "3") (pinfunction "3_3") (pintype "passive"))
      (node (ref "SW3") (pin "4") (pinfunction "4_4") (pintype "passive"))
      (node (ref "SW4") (pin "3") (pinfunction "3_3") (pintype "passive"))
      (node (ref "SW4") (pin "4") (pinfunction "4_4") (pintype "passive"))
      (node (ref "U1") (pin "13") (pinfunction "GND_13") (pintype "passive"))
      (node (ref "U1") (pin "21") (pinfunction "GND_21") (pintype "passive"))
      (node (ref "U1") (pin "3") (pinfunction "GND_3") (pintype "passive"))
      (node (ref "U2") (pin "2") (pinfunction "GND_2") (pintype "power_in"))
      (node (ref "U2") (pin "4") (pinfunction "GND_4") (pintype "power_in"))
      (node (ref "U3") (pin "1") (pinfunction "GND_1_1") (pintype "passive"))
      (node (ref "U3") (pin "2") (pinfunction "GND_2_2") (pintype "passive"))
      (node (ref "U3") (pin "42") (pinfunction "GND_42_42") (pintype "passive"))
      (node (ref "U3") (pin "43") (pinfunction "GND-43_43") (pintype "passive"))
      (node (ref "U3") (pin "46") (pinfunction "GND_46_46") (pintype "passive"))
      (node (ref "U3") (pin "47") (pinfunction "GND_47_47") (pintype "passive"))
      (node (ref "U3") (pin "48") (pinfunction "GND_48_48") (pintype "passive"))
      (node (ref "U3") (pin "49") (pinfunction "GND_49_49") (pintype "passive"))
      (node (ref "U3") (pin "50") (pinfunction "GND_50_50") (pintype "passive"))
      (node (ref "U3") (pin "51") (pinfunction "GND_51_51") (pintype "passive"))
      (node (ref "U3") (pin "52") (pinfunction "GND_52_52") (pintype "passive"))
      (node (ref "U3") (pin "53") (pinfunction "GND_53_53") (pintype "passive"))
      (node (ref "U3") (pin "54") (pinfunction "GND_54_54") (pintype "passive"))
      (node (ref "U3") (pin "55") (pinfunction "GND_55_55") (pintype "passive"))
      (node (ref "U3") (pin "56") (pinfunction "GND_56_56") (pintype "passive"))
      (node (ref "U3") (pin "57") (pinfunction "GND_57_57") (pintype "passive"))
      (node (ref "U3") (pin "58") (pinfunction "GND_58_58") (pintype "passive"))
      (node (ref "U3") (pin "59") (pinfunction "GND_59_59") (pintype "passive"))
      (node (ref "U3") (pin "60") (pinfunction "GND_60_60") (pintype "passive"))
      (node (ref "U3") (pin "61") (pinfunction "GND_61_61") (pintype "passive"))
      (node (ref "U3") (pin "62") (pinfunction "GND_62_62") (pintype "passive"))
      (node (ref "U3") (pin "63") (pinfunction "GND_63_63") (pintype "passive"))
      (node (ref "U3") (pin "64") (pinfunction "GND_64_64") (pintype "passive"))
      (node (ref "U3") (pin "65") (pinfunction "GND_65_65") (pintype "passive"))
      (node (ref "U3") (pin "66") (pinfunction "GND_66_66") (pintype "passive"))
      (node (ref "U3") (pin "67") (pinfunction "GND_67_67") (pintype "passive"))
      (node (ref "U3") (pin "68") (pinfunction "GND_68_68") (pintype "passive"))
      (node (ref "U3") (pin "69") (pinfunction "GND_69_69") (pintype "passive"))
      (node (ref "U3") (pin "70") (pinfunction "GND_70_70") (pintype "passive"))
      (node (ref "U3") (pin "71") (pinfunction "GND_71_71") (pintype "passive"))
      (node (ref "U3") (pin "72") (pinfunction "GND_72_72") (pintype "passive"))
      (node (ref "U3") (pin "73") (pinfunction "GND_73_73") (pintype "passive"))
    )
    (net (code "64") (name "Net-(D4-Pad2)") (class "Default")
      (node (ref "D4") (pin "2") (pinfunction "2_2") (pintype "passive"))
      (node (ref "R5") (pin "1") (pinfunction "1_1") (pintype "passive"))
    )
    (net (code "65") (name "Net-(D8-Pad2)") (class "Default")
      (node (ref "D8") (pin "2") (pinfunction "2_2") (pintype "passive"))
      (node (ref "R15") (pin "1") (pinfunction "1_1") (pintype "passive"))
    )
    (net (code "66") (name "Net-(J1-CC1)") (class "Default")
      (node (ref "J1") (pin "A5") (pinfunction "CC1_A5") (pintype "passive"))
      (node (ref "R4") (pin "2") (pinfunction "2_2") (pintype "passive"))
    )
    (net (code "67") (name "Net-(J1-CC2)") (class "Default")
      (node (ref "J1") (pin "B5") (pinfunction "CC2_B5") (pintype "passive"))
      (node (ref "R70") (pin "2") (pinfunction "2_2") (pintype "passive"))
    )
    (net (code "68") (name "Net-(J3-CC1)") (class "Default")
      (node (ref "J3") (pin "A5") (pinfunction "CC1_A5") (pintype "passive"))
      (node (ref "R13") (pin "2") (pinfunction "2_2") (pintype "passive"))
    )
    (net (code "69") (name "Net-(J3-CC2)") (class "Default")
      (node (ref "J3") (pin "B5") (pinfunction "CC2_B5") (pintype "passive"))
      (node (ref "R12") (pin "2") (pinfunction "2_2") (pintype "passive"))
    )
    (net (code "70") (name "Net-(Q1-B)") (class "Default")
      (node (ref "Q1") (pin "1") (pinfunction "B_1") (pintype "passive"))
      (node (ref "R21") (pin "1") (pinfunction "1_1") (pintype "passive"))
    )
    (net (code "71") (name "Net-(Q2-B)") (class "Default")
      (node (ref "Q2") (pin "1") (pinfunction "B_1") (pintype "passive"))
      (node (ref "R26") (pin "1") (pinfunction "1_1") (pintype "passive"))
    )
    (net (code "72") (name "Net-(U1-CBUS0)") (class "Default")
      (node (ref "R10") (pin "2") (pinfunction "2_2") (pintype "passive"))
      (node (ref "U1") (pin "15") (pinfunction "CBUS0_15") (pintype "passive"))
    )
    (net (code "73") (name "Net-(U1-~{RESET})") (class "Default")
      (node (ref "C5") (pin "1") (pinfunction "1_1") (pintype "passive"))
      (node (ref "R9") (pin "2") (pinfunction "2_2") (pintype "passive"))
      (node (ref "U1") (pin "11") (pinfunction "~{RESET}_11") (pintype "passive"))
    )
    (net (code "74") (name "unconnected-(J1-SBU1-PadA8)") (class "Default")
      (node (ref "J1") (pin "A8") (pinfunction "SBU1_A8") (pintype "passive+no_connect"))
    )
    (net (code "75") (name "unconnected-(J1-SBU2-PadB8)") (class "Default")
      (node (ref "J1") (pin "B8") (pinfunction "SBU2_B8") (pintype "passive+no_connect"))
    )
    (net (code "76") (name "unconnected-(J3-SBU1-PadA8)") (class "Default")
      (node (ref "J3") (pin "A8") (pinfunction "SBU1_A8") (pintype "passive+no_connect"))
    )
    (net (code "77") (name "unconnected-(J3-SBU2-PadB8)") (class "Default")
      (node (ref "J3") (pin "B8") (pinfunction "SBU2_B8") (pintype "passive+no_connect"))
    )
    (net (code "78") (name "unconnected-(J5-Pad24)") (class "Default")
      (node (ref "J5") (pin "24") (pinfunction "24_24") (pintype "passive"))
    )
    (net (code "79") (name "unconnected-(U1-CBUS1-Pad14)") (class "Default")
      (node (ref "U1") (pin "14") (pinfunction "CBUS1_14") (pintype "passive+no_connect"))
    )
    (net (code "80") (name "unconnected-(U1-CBUS2-Pad7)") (class "Default")
      (node (ref "U1") (pin "7") (pinfunction "CBUS2_7") (pintype "passive+no_connect"))
    )
    (net (code "81") (name "unconnected-(U1-~{CTS}-Pad6)") (class "Default")
      (node (ref "U1") (pin "6") (pinfunction "~{CTS}_6") (pintype "passive+no_connect"))
    )
    (net (code "82") (name "unconnected-(U1-~{DCD}-Pad5)") (class "Default")
      (node (ref "U1") (pin "5") (pinfunction "~{DCD}_5") (pintype "passive+no_connect"))
    )
    (net (code "83") (name "unconnected-(U1-~{DSR}-Pad4)") (class "Default")
      (node (ref "U1") (pin "4") (pinfunction "~{DSR}_4") (pintype "passive+no_connect"))
    )
    (net (code "84") (name "unconnected-(U1-~{RI}-Pad2)") (class "Default")
      (node (ref "U1") (pin "2") (pinfunction "~{RI}_2") (pintype "passive+no_connect"))
    )
  )
)
